# mps-v1.net
KiCad netlist of a schematic drawn in EAGLE
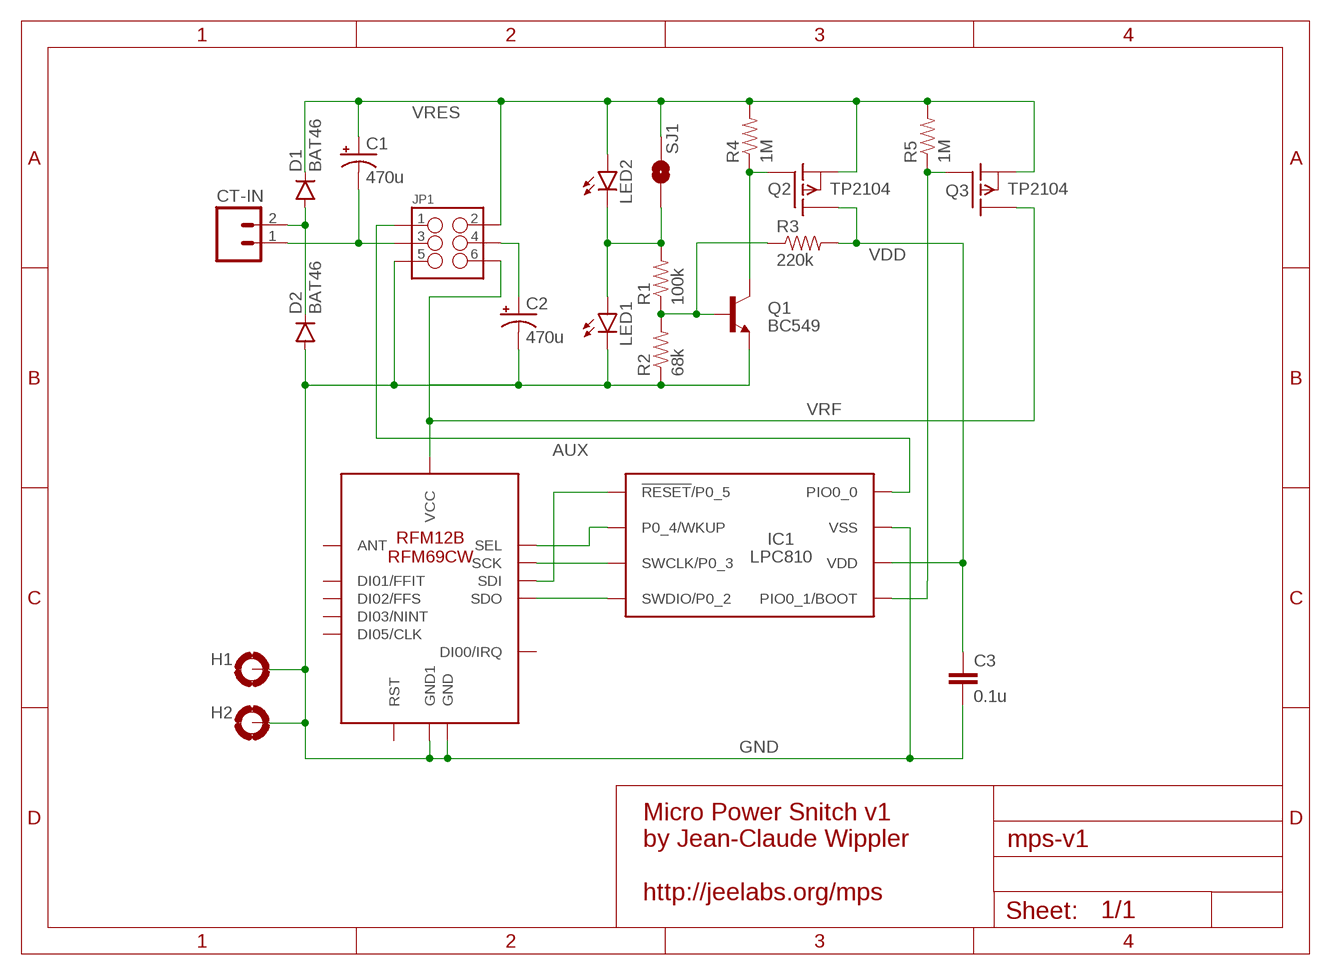
[diagram p0: schematic, sheet 1]

(export (version "E")
  (design (tool "Eeschema 10.0.6"))
  (components
    (comp (ref "C1")
      (value "470u")
      (footprint "eagle-import:CPOL-RADIAL-100UF-25V")
      (libsource (lib "eagle-import") (part "CAP_POLPTH1"))
    )
    (comp (ref "C2")
      (value "470u")
      (footprint "eagle-import:CPOL-RADIAL-100UF-25V")
      (libsource (lib "eagle-import") (part "CAP_POLPTH1"))
    )
    (comp (ref "C3")
      (value "0.1u")
      (footprint "eagle-import:CAP-PTH-SMALL")
      (libsource (lib "eagle-import") (part "CAPPTH"))
    )
    (comp (ref "CT-IN")
      (value "M023.5MM")
      (footprint "eagle-import:SCREWTERMINAL-3.5MM-2")
      (libsource (lib "eagle-import") (part "M023.5MM"))
    )
    (comp (ref "D1")
      (value "BAT46")
      (footprint "eagle-import:DIODE-1N4148")
      (libsource (lib "eagle-import") (part "DIODE1N4148"))
    )
    (comp (ref "D2")
      (value "BAT46")
      (footprint "eagle-import:DIODE-1N4148")
      (libsource (lib "eagle-import") (part "DIODE1N4148"))
    )
    (comp (ref "H1")
      (value "MOUNT-PAD-ROUND2.8")
      (footprint "eagle-import:2,8-PAD")
      (libsource (lib "eagle-import") (part "MOUNT-PAD-ROUND2.8"))
    )
    (comp (ref "H2")
      (value "MOUNT-PAD-ROUND2.8")
      (footprint "eagle-import:2,8-PAD")
      (libsource (lib "eagle-import") (part "MOUNT-PAD-ROUND2.8"))
    )
    (comp (ref "IC1")
      (value "LPC810")
      (footprint "eagle-import:DIP8")
      (libsource (lib "eagle-import") (part "LPC810M021FN8"))
    )
    (comp (ref "JP1")
      (value "M03X2NO_SILK")
      (footprint "eagle-import:2X3-NS")
      (libsource (lib "eagle-import") (part "M03X2NO_SILK"))
    )
    (comp (ref "LED1")
      (value "LED3MM")
      (footprint "eagle-import:LED3MM")
      (libsource (lib "eagle-import") (part "LED3MM"))
    )
    (comp (ref "LED2")
      (value "LED3MM")
      (footprint "eagle-import:LED3MM")
      (libsource (lib "eagle-import") (part "LED3MM"))
    )
    (comp (ref "Q1")
      (value "BC549")
      (footprint "eagle-import:TO92")
      (libsource (lib "eagle-import") (part "BC547"))
    )
    (comp (ref "Q2")
      (value "TP2104")
      (footprint "eagle-import:TO92")
      (libsource (lib "eagle-import") (part "BSS110"))
    )
    (comp (ref "Q3")
      (value "TP2104")
      (footprint "eagle-import:TO92")
      (libsource (lib "eagle-import") (part "BSS110"))
    )
    (comp (ref "R1")
      (value "100k")
      (footprint "eagle-import:AXIAL-0.3")
      (libsource (lib "eagle-import") (part "RESISTORAXIAL-0.3"))
    )
    (comp (ref "R2")
      (value "68k")
      (footprint "eagle-import:AXIAL-0.3")
      (libsource (lib "eagle-import") (part "RESISTORAXIAL-0.3"))
    )
    (comp (ref "R3")
      (value "220k")
      (footprint "eagle-import:AXIAL-0.3")
      (libsource (lib "eagle-import") (part "RESISTORAXIAL-0.3"))
    )
    (comp (ref "R4")
      (value "1M")
      (footprint "eagle-import:AXIAL-0.3")
      (libsource (lib "eagle-import") (part "RESISTORAXIAL-0.3"))
    )
    (comp (ref "R5")
      (value "1M")
      (footprint "eagle-import:AXIAL-0.3")
      (libsource (lib "eagle-import") (part "RESISTORAXIAL-0.3"))
    )
    (comp (ref "RFM12B/69CW")
      (value "RFM12B/69CW")
      (footprint "eagle-import:RFM12B_69CW")
      (libsource (lib "eagle-import") (part "RFM12B/69CW"))
    )
    (comp (ref "SJ1")
      (value "JUMPER-PAD-2-NO")
      (footprint "eagle-import:PAD-JUMPER-2-NO_NO_SILK")
      (libsource (lib "eagle-import") (part "JUMPER-PAD-2-NO"))
    )
  )
  (nets
    (net (code "1") (name "/AUX") (class "Default")
      (node (ref "IC1") (pin "P$8") (pinfunction "PIO0_0_P$8") (pintype "bidirectional"))
      (node (ref "JP1") (pin "1") (pinfunction "1_1") (pintype "bidirectional"))
    )
    (net (code "2") (name "/GND") (class "Default")
      (node (ref "C2") (pin "2") (pinfunction "-_2") (pintype "passive"))
      (node (ref "C3") (pin "2") (pinfunction "2_2") (pintype "passive"))
      (node (ref "D2") (pin "A") (pinfunction "A_A") (pintype "passive"))
      (node (ref "H1") (pin "B2,8") (pinfunction "MOUNT_B2,8") (pintype "passive"))
      (node (ref "H2") (pin "B2,8") (pinfunction "MOUNT_B2,8") (pintype "passive"))
      (node (ref "IC1") (pin "P$7") (pinfunction "VSS_P$7") (pintype "bidirectional"))
      (node (ref "JP1") (pin "5") (pinfunction "5_5") (pintype "bidirectional"))
      (node (ref "LED1") (pin "K") (pinfunction "C_K") (pintype "passive"))
      (node (ref "Q1") (pin "1") (pinfunction "E_1") (pintype "passive"))
      (node (ref "R2") (pin "P$1") (pinfunction "1_P$1") (pintype "passive"))
      (node (ref "RFM12B/69CW") (pin "GND") (pinfunction "GND_GND") (pintype "power_in"))
      (node (ref "RFM12B/69CW") (pin "GND1") (pinfunction "GND1_GND1") (pintype "power_in"))
    )
    (net (code "3") (name "/VDD") (class "Default")
      (node (ref "C3") (pin "1") (pinfunction "1_1") (pintype "passive"))
      (node (ref "IC1") (pin "P$6") (pinfunction "VDD_P$6") (pintype "bidirectional"))
      (node (ref "Q2") (pin "3") (pinfunction "D_3") (pintype "passive"))
      (node (ref "R3") (pin "P$2") (pinfunction "2_P$2") (pintype "passive"))
    )
    (net (code "4") (name "/VRES") (class "Default")
      (node (ref "C1") (pin "1") (pinfunction "+_1") (pintype "passive"))
      (node (ref "D1") (pin "C") (pinfunction "C_C") (pintype "passive"))
      (node (ref "JP1") (pin "2") (pinfunction "2_2") (pintype "bidirectional"))
      (node (ref "LED2") (pin "A") (pinfunction "A_A") (pintype "passive"))
      (node (ref "Q2") (pin "1") (pinfunction "S_1") (pintype "passive"))
      (node (ref "Q3") (pin "1") (pinfunction "S_1") (pintype "passive"))
      (node (ref "R4") (pin "P$2") (pinfunction "2_P$2") (pintype "passive"))
      (node (ref "R5") (pin "P$2") (pinfunction "2_P$2") (pintype "passive"))
      (node (ref "SJ1") (pin "2") (pinfunction "2_2") (pintype "passive"))
    )
    (net (code "5") (name "/VRF") (class "Default")
      (node (ref "JP1") (pin "6") (pinfunction "6_6") (pintype "bidirectional"))
      (node (ref "Q3") (pin "3") (pinfunction "D_3") (pintype "passive"))
      (node (ref "RFM12B/69CW") (pin "VDD") (pinfunction "VCC_VDD") (pintype "power_in"))
    )
    (net (code "6") (name "Net-(C1--)") (class "Default")
      (node (ref "C1") (pin "2") (pinfunction "-_2") (pintype "passive"))
      (node (ref "CT-IN") (pin "1") (pinfunction "1_1") (pintype "passive"))
      (node (ref "JP1") (pin "3") (pinfunction "3_3") (pintype "bidirectional"))
    )
    (net (code "7") (name "Net-(C2-+)") (class "Default")
      (node (ref "C2") (pin "1") (pinfunction "+_1") (pintype "passive"))
      (node (ref "JP1") (pin "4") (pinfunction "4_4") (pintype "bidirectional"))
    )
    (net (code "8") (name "Net-(CT-IN-Pad2)") (class "Default")
      (node (ref "CT-IN") (pin "2") (pinfunction "2_2") (pintype "passive"))
      (node (ref "D1") (pin "A") (pinfunction "A_A") (pintype "passive"))
      (node (ref "D2") (pin "C") (pinfunction "C_C") (pintype "passive"))
    )
    (net (code "9") (name "Net-(IC1-P0_4{slash}WKUP)") (class "Default")
      (node (ref "IC1") (pin "P$2") (pinfunction "P0_4/WKUP_P$2") (pintype "bidirectional"))
      (node (ref "RFM12B/69CW") (pin "SEL") (pinfunction "SEL_SEL") (pintype "input"))
    )
    (net (code "10") (name "Net-(IC1-PIO0_1{slash}BOOT)") (class "Default")
      (node (ref "IC1") (pin "P$5") (pinfunction "PIO0_1/BOOT_P$5") (pintype "bidirectional"))
      (node (ref "Q3") (pin "2") (pinfunction "G_2") (pintype "passive"))
      (node (ref "R5") (pin "P$1") (pinfunction "1_P$1") (pintype "passive"))
    )
    (net (code "11") (name "Net-(IC1-SWCLK{slash}P0_3)") (class "Default")
      (node (ref "IC1") (pin "P$3") (pinfunction "SWCLK/P0_3_P$3") (pintype "bidirectional"))
      (node (ref "RFM12B/69CW") (pin "SCK") (pinfunction "SCK_SCK") (pintype "input"))
    )
    (net (code "12") (name "Net-(IC1-SWDIO{slash}P0_2)") (class "Default")
      (node (ref "IC1") (pin "P$4") (pinfunction "SWDIO/P0_2_P$4") (pintype "bidirectional"))
      (node (ref "RFM12B/69CW") (pin "SDO") (pinfunction "SDO_SDO") (pintype "output"))
    )
    (net (code "13") (name "Net-(IC1-~{RESET}{slash}P0_5)") (class "Default")
      (node (ref "IC1") (pin "P$1") (pinfunction "~{RESET}/P0_5_P$1") (pintype "bidirectional"))
      (node (ref "RFM12B/69CW") (pin "SDI") (pinfunction "SDI_SDI") (pintype "input"))
    )
    (net (code "14") (name "Net-(LED2-C)") (class "Default")
      (node (ref "LED1") (pin "A") (pinfunction "A_A") (pintype "passive"))
      (node (ref "LED2") (pin "K") (pinfunction "C_K") (pintype "passive"))
      (node (ref "R1") (pin "P$2") (pinfunction "2_P$2") (pintype "passive"))
      (node (ref "SJ1") (pin "1") (pinfunction "1_1") (pintype "passive"))
    )
    (net (code "15") (name "Net-(Q1-B)") (class "Default")
      (node (ref "Q1") (pin "2") (pinfunction "B_2") (pintype "passive"))
      (node (ref "R1") (pin "P$1") (pinfunction "1_P$1") (pintype "passive"))
      (node (ref "R2") (pin "P$2") (pinfunction "2_P$2") (pintype "passive"))
      (node (ref "R3") (pin "P$1") (pinfunction "1_P$1") (pintype "passive"))
    )
    (net (code "16") (name "Net-(Q1-C)") (class "Default")
      (node (ref "Q1") (pin "3") (pinfunction "C_3") (pintype "passive"))
      (node (ref "Q2") (pin "2") (pinfunction "G_2") (pintype "passive"))
      (node (ref "R4") (pin "P$1") (pinfunction "1_P$1") (pintype "passive"))
    )
    (net (code "17") (name "unconnected-(RFM12B/69CW-DI00{slash}IRQ-PadIRQ)") (class "Default")
      (node (ref "RFM12B/69CW") (pin "IRQ") (pinfunction "DI00/IRQ_IRQ") (pintype "open_collector"))
    )
    (net (code "18") (name "unconnected-(RFM12B/69CW-DI01{slash}FFIT-PadFFIT)") (class "Default")
      (node (ref "RFM12B/69CW") (pin "FFIT") (pinfunction "DI01/FFIT_FFIT") (pintype "passive"))
    )
    (net (code "19") (name "unconnected-(RFM12B/69CW-DI02{slash}FFS-PadFFS)") (class "Default")
      (node (ref "RFM12B/69CW") (pin "FFS") (pinfunction "DI02/FFS_FFS") (pintype "bidirectional"))
    )
    (net (code "20") (name "unconnected-(RFM12B/69CW-DI03{slash}NINT-PadNINT)") (class "Default")
      (node (ref "RFM12B/69CW") (pin "NINT") (pinfunction "DI03/NINT_NINT") (pintype "passive"))
    )
    (net (code "21") (name "unconnected-(RFM12B/69CW-DI05{slash}CLK-PadCLK)") (class "Default")
      (node (ref "RFM12B/69CW") (pin "CLK") (pinfunction "DI05/CLK_CLK") (pintype "passive"))
    )
    (net (code "22") (name "unconnected-(RFM12B/69CW-PadANT)") (class "Default")
      (node (ref "RFM12B/69CW") (pin "ANT") (pinfunction "ANT_ANT") (pintype "passive"))
    )
    (net (code "23") (name "unconnected-(RFM12B/69CW-PadRST)") (class "Default")
      (node (ref "RFM12B/69CW") (pin "RST") (pinfunction "RST_RST") (pintype "open_collector"))
    )
  )
)
